# FletchRedesignApril1.net
KiCad netlist of a schematic drawn in EAGLE
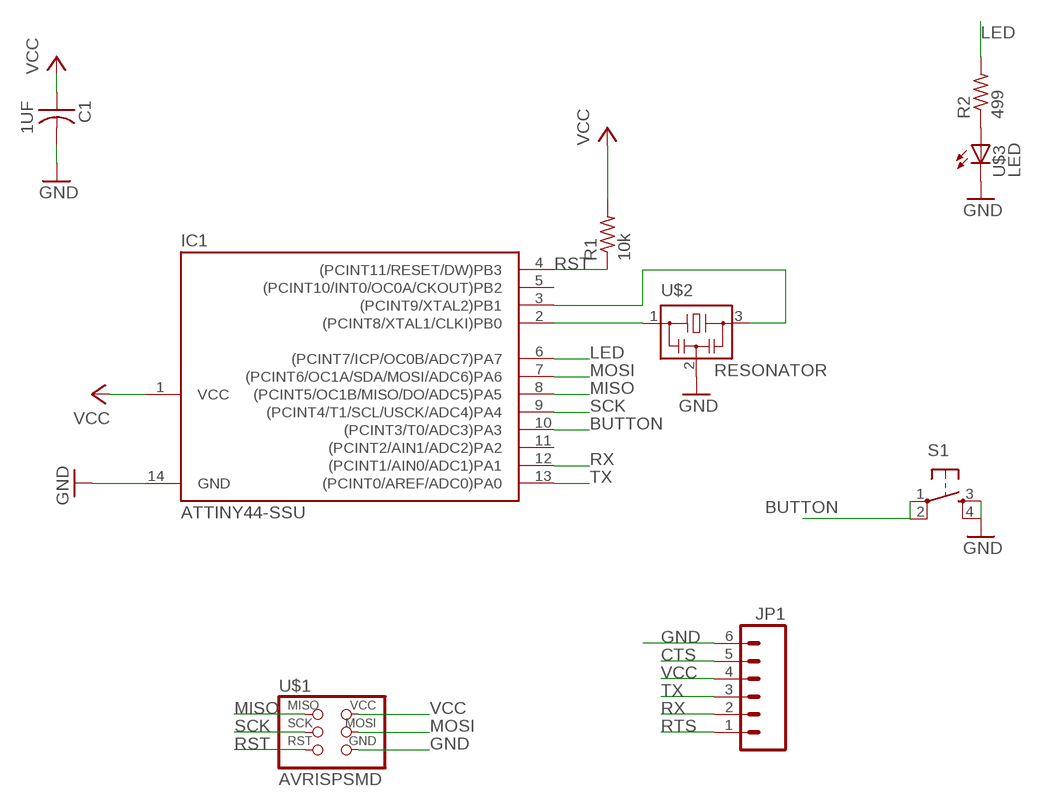
[diagram p0: schematic, sheet 1]

(export (version "E")
  (design (tool "Eeschema 10.0.6"))
  (components
    (comp (ref "C1")
      (value "1UF")
      (footprint "eagle-import:C1206FAB")
      (libsource (lib "eagle-import") (part "CAP-US1206FAB"))
    )
    (comp (ref "IC1")
      (value "ATTINY44-SSU")
      (footprint "eagle-import:SOIC14")
      (libsource (lib "eagle-import") (part "ATTINY44-SSU"))
    )
    (comp (ref "JP1")
      (value "M06SMD")
      (footprint "eagle-import:1X06-SMD")
      (libsource (lib "eagle-import") (part "M06SMD"))
    )
    (comp (ref "R1")
      (value "10k")
      (footprint "eagle-import:R1206")
      (libsource (lib "eagle-import") (part "RES-US1206"))
    )
    (comp (ref "R2")
      (value "499")
      (footprint "eagle-import:R1206")
      (libsource (lib "eagle-import") (part "RES-US1206"))
    )
    (comp (ref "S1")
      (value "6MM_SWITCH6MM_SWITCH")
      (footprint "eagle-import:6MM_SWITCH")
      (libsource (lib "eagle-import") (part "6MM_SWITCH6MM_SWITCH"))
    )
    (comp (ref "U$1")
      (value "AVRISPSMD")
      (footprint "eagle-import:2X03SMD")
      (libsource (lib "eagle-import") (part "AVRISPSMD"))
    )
    (comp (ref "U$2")
      (value "RESONATOR")
      (footprint "eagle-import:EFOBM")
      (libsource (lib "eagle-import") (part "RESONATOR"))
    )
    (comp (ref "U$3")
      (value "LED")
      (footprint "eagle-import:LED1206")
      (libsource (lib "eagle-import") (part "LED"))
    )
  )
  (nets
    (net (code "1") (name "/BUTTON") (class "Default")
      (node (ref "IC1") (pin "10") (pinfunction "(PCINT3/T0/ADC3)PA3_10") (pintype "bidirectional"))
      (node (ref "S1") (pin "1") (pinfunction "P_1") (pintype "passive"))
      (node (ref "S1") (pin "2") (pinfunction "P1_2") (pintype "passive"))
    )
    (net (code "2") (name "/CTS") (class "Default")
      (node (ref "JP1") (pin "5") (pinfunction "5_5") (pintype "passive"))
    )
    (net (code "3") (name "/LED") (class "Default")
      (node (ref "IC1") (pin "6") (pinfunction "(PCINT7/ICP/OC0B/ADC7)PA7_6") (pintype "bidirectional"))
      (node (ref "R2") (pin "2") (pinfunction "2_2") (pintype "passive"))
    )
    (net (code "4") (name "/MISO") (class "Default")
      (node (ref "IC1") (pin "8") (pinfunction "(PCINT5/OC1B/MISO/DO/ADC5)PA5_8") (pintype "bidirectional"))
      (node (ref "U$1") (pin "1") (pinfunction "MISO_1") (pintype "passive"))
    )
    (net (code "5") (name "/MOSI") (class "Default")
      (node (ref "IC1") (pin "7") (pinfunction "(PCINT6/OC1A/SDA/MOSI/ADC6)PA6_7") (pintype "bidirectional"))
      (node (ref "U$1") (pin "4") (pinfunction "MOSI_4") (pintype "passive"))
    )
    (net (code "6") (name "/RST") (class "Default")
      (node (ref "IC1") (pin "4") (pinfunction "(PCINT11/RESET/DW)PB3_4") (pintype "bidirectional"))
      (node (ref "R1") (pin "1") (pinfunction "1_1") (pintype "passive"))
      (node (ref "U$1") (pin "5") (pinfunction "RST_5") (pintype "passive"))
    )
    (net (code "7") (name "/RTS") (class "Default")
      (node (ref "JP1") (pin "1") (pinfunction "1_1") (pintype "passive"))
    )
    (net (code "8") (name "/RX") (class "Default")
      (node (ref "IC1") (pin "12") (pinfunction "(PCINT1/AIN0/ADC1)PA1_12") (pintype "bidirectional"))
      (node (ref "JP1") (pin "2") (pinfunction "2_2") (pintype "passive"))
    )
    (net (code "9") (name "/SCK") (class "Default")
      (node (ref "IC1") (pin "9") (pinfunction "(PCINT4/T1/SCL/USCK/ADC4)PA4_9") (pintype "bidirectional"))
      (node (ref "U$1") (pin "3") (pinfunction "SCK_3") (pintype "passive"))
    )
    (net (code "10") (name "/TX") (class "Default")
      (node (ref "IC1") (pin "13") (pinfunction "(PCINT0/AREF/ADC0)PA0_13") (pintype "bidirectional"))
      (node (ref "JP1") (pin "3") (pinfunction "3_3") (pintype "passive"))
    )
    (net (code "11") (name "GND") (class "Default")
      (node (ref "C1") (pin "2") (pinfunction "2_2") (pintype "passive"))
      (node (ref "IC1") (pin "14") (pinfunction "GND_14") (pintype "power_in"))
      (node (ref "JP1") (pin "6") (pinfunction "6_6") (pintype "passive"))
      (node (ref "S1") (pin "3") (pinfunction "S_3") (pintype "passive"))
      (node (ref "S1") (pin "4") (pinfunction "S1_4") (pintype "passive"))
      (node (ref "U$1") (pin "6") (pinfunction "GND_6") (pintype "passive"))
      (node (ref "U$2") (pin "2") (pinfunction "2_2") (pintype "passive"))
      (node (ref "U$3") (pin "2") (pinfunction "C_2") (pintype "passive"))
    )
    (net (code "12") (name "Net-(IC1-(PCINT8{slash}XTAL1{slash}CLKI)PB0)") (class "Default")
      (node (ref "IC1") (pin "2") (pinfunction "(PCINT8/XTAL1/CLKI)PB0_2") (pintype "bidirectional"))
      (node (ref "U$2") (pin "1") (pinfunction "1_1") (pintype "passive"))
    )
    (net (code "13") (name "Net-(IC1-(PCINT9{slash}XTAL2)PB1)") (class "Default")
      (node (ref "IC1") (pin "3") (pinfunction "(PCINT9/XTAL2)PB1_3") (pintype "bidirectional"))
      (node (ref "U$2") (pin "3") (pinfunction "3_3") (pintype "passive"))
    )
    (net (code "14") (name "Net-(U$3-A)") (class "Default")
      (node (ref "R2") (pin "1") (pinfunction "1_1") (pintype "passive"))
      (node (ref "U$3") (pin "1") (pinfunction "A_1") (pintype "passive"))
    )
    (net (code "15") (name "VCC") (class "Default")
      (node (ref "C1") (pin "1") (pinfunction "1_1") (pintype "passive"))
      (node (ref "IC1") (pin "1") (pinfunction "VCC_1") (pintype "power_in"))
      (node (ref "JP1") (pin "4") (pinfunction "4_4") (pintype "passive"))
      (node (ref "R1") (pin "2") (pinfunction "2_2") (pintype "passive"))
      (node (ref "U$1") (pin "2") (pinfunction "VCC_2") (pintype "passive"))
    )
    (net (code "16") (name "unconnected-(IC1-(PCINT2{slash}AIN1{slash}ADC2)PA2-Pad11)") (class "Default")
      (node (ref "IC1") (pin "11") (pinfunction "(PCINT2/AIN1/ADC2)PA2_11") (pintype "bidirectional"))
    )
    (net (code "17") (name "unconnected-(IC1-(PCINT10{slash}INT0{slash}OC0A{slash}CKOUT)PB2-Pad5)") (class "Default")
      (node (ref "IC1") (pin "5") (pinfunction "(PCINT10/INT0/OC0A/CKOUT)PB2_5") (pintype "bidirectional"))
    )
  )
)
